# MC_2015.net
KiCad netlist of a schematic drawn in EAGLE
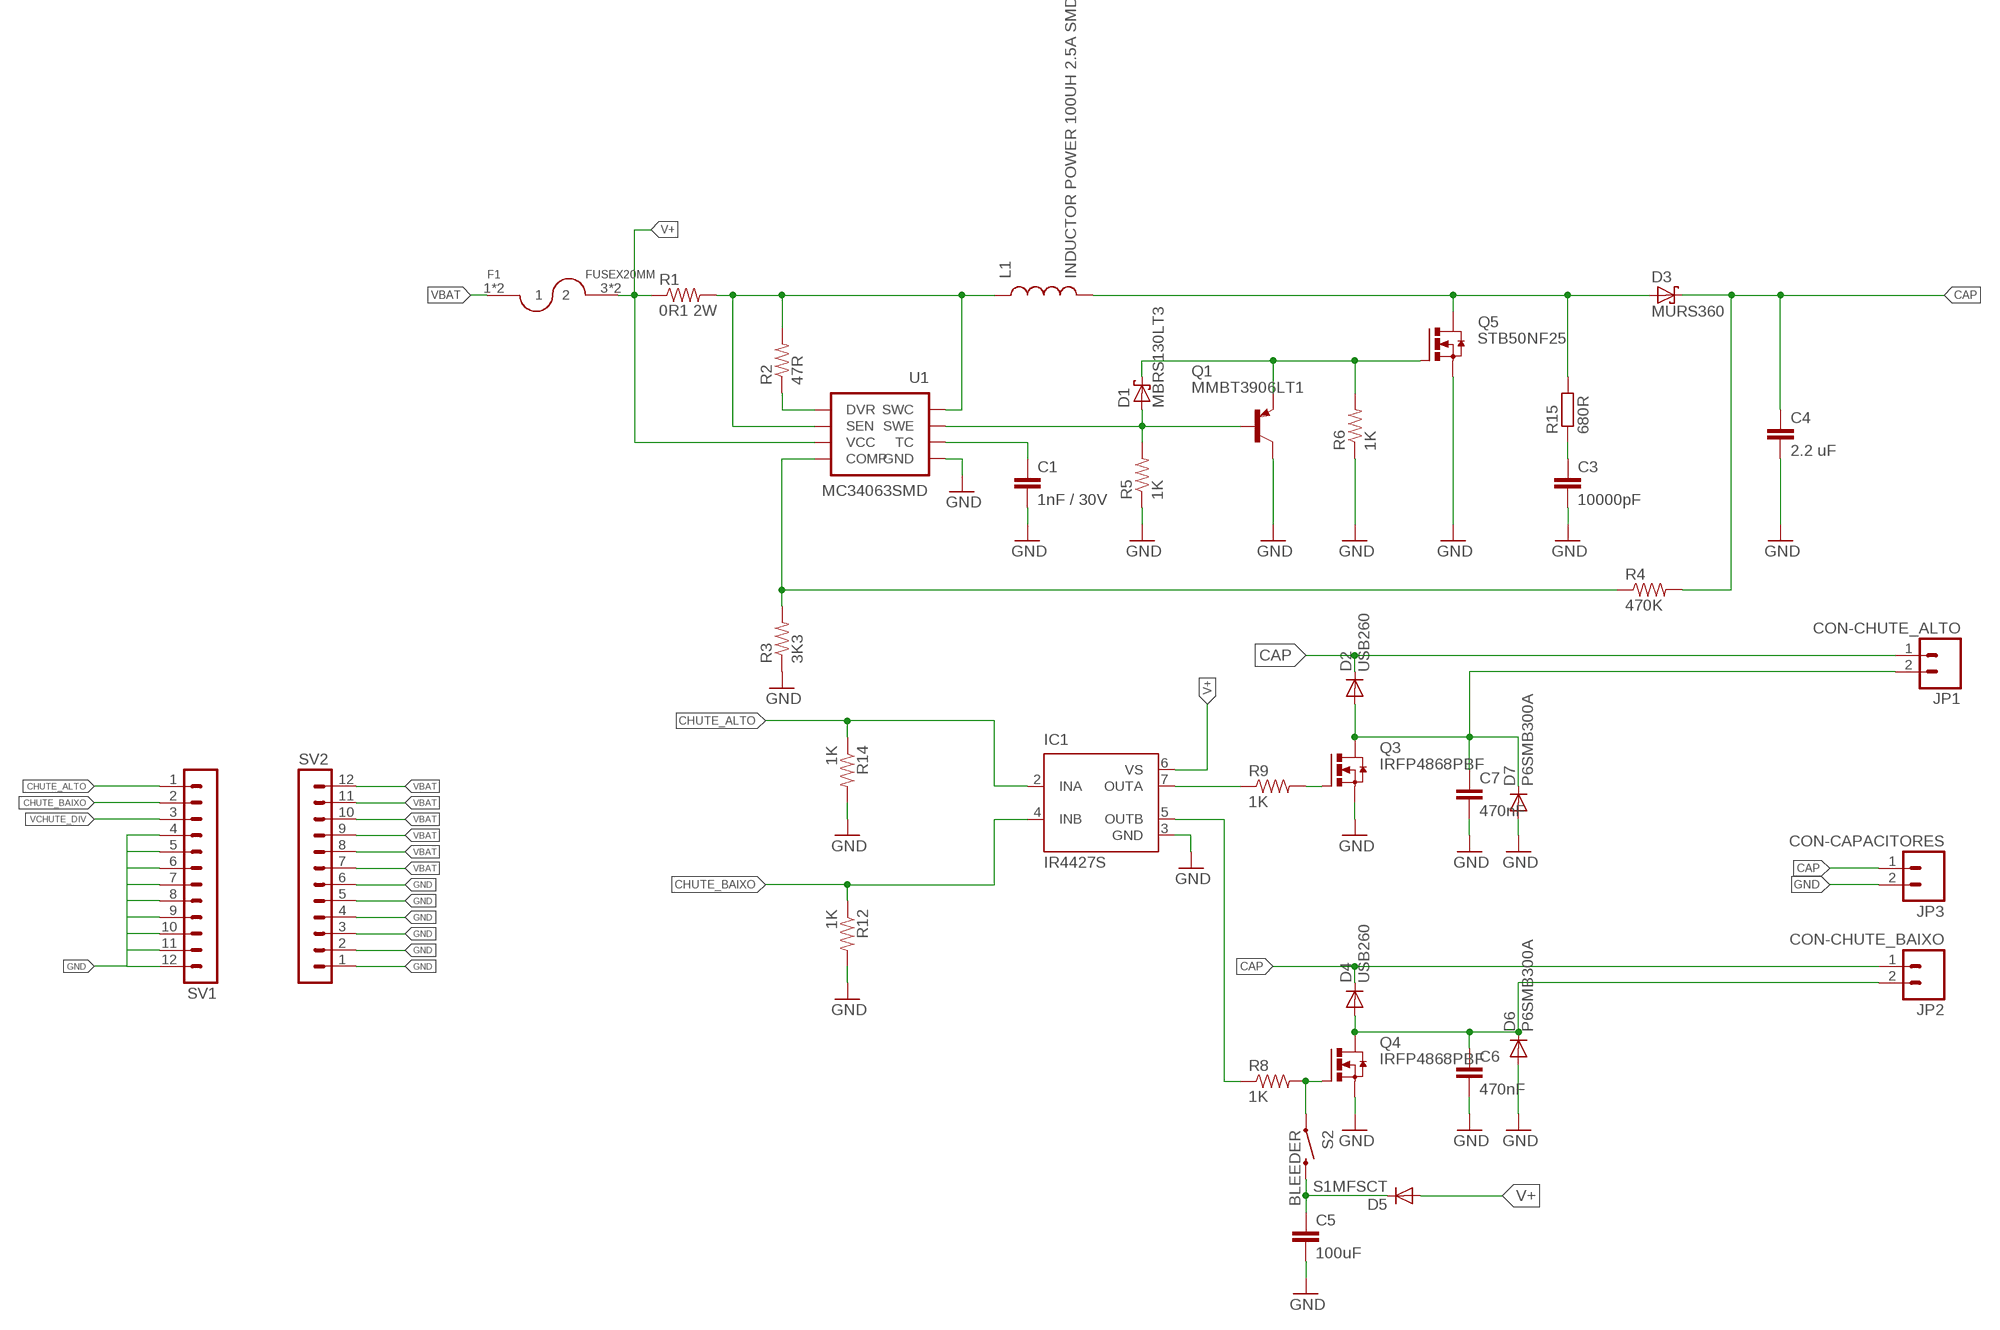
[diagram p0: schematic, sheet 1]

(export (version "E")
  (design (tool "Eeschema 10.0.6"))
  (components
    (comp (ref "C1")
      (value "1nF / 30V")
      (footprint "eagle-import:0805")
      (libsource (lib "eagle-import") (part "CAP0805"))
    )
    (comp (ref "C3")
      (value "10000pF")
      (footprint "eagle-import:1210")
      (libsource (lib "eagle-import") (part "SparkFun-Passives_CAP1210"))
    )
    (comp (ref "C4")
      (value "2.2 uF")
      (footprint "eagle-import:C2220K")
      (libsource (lib "eagle-import") (part "resistor_C-EUC2220K"))
    )
    (comp (ref "C5")
      (value "100uF")
      (footprint "eagle-import:C1210")
      (libsource (lib "eagle-import") (part "resistor_C-EUC1210"))
    )
    (comp (ref "C6")
      (value "470nF")
      (footprint "eagle-import:C1812")
      (libsource (lib "eagle-import") (part "C-EUC1812"))
    )
    (comp (ref "C7")
      (value "470nF")
      (footprint "eagle-import:C1812")
      (libsource (lib "eagle-import") (part "C-EUC1812"))
    )
    (comp (ref "D1")
      (value "MBRS130LT3")
      (footprint "eagle-import:SMB")
      (libsource (lib "eagle-import") (part "MBRS130LT3"))
    )
    (comp (ref "D2")
      (value "USB260")
      (footprint "eagle-import:SMB")
      (libsource (lib "eagle-import") (part "DIODE-SMB"))
    )
    (comp (ref "D3")
      (value "MURS360")
      (footprint "eagle-import:SMC")
      (libsource (lib "eagle-import") (part "SCHOTTKY-DIODESMC"))
    )
    (comp (ref "D4")
      (value "USB260")
      (footprint "eagle-import:SMB")
      (libsource (lib "eagle-import") (part "DIODE-SMB"))
    )
    (comp (ref "D5")
      (value "S1MFSCT")
      (footprint "eagle-import:SMA-DIODE")
      (libsource (lib "eagle-import") (part "DIODESMA"))
    )
    (comp (ref "D6")
      (value "P6SMB300A")
      (footprint "eagle-import:SMB")
      (libsource (lib "eagle-import") (part "DIODE-SMB"))
    )
    (comp (ref "D7")
      (value "P6SMB300A")
      (footprint "eagle-import:SMB")
      (libsource (lib "eagle-import") (part "DIODE-SMB"))
    )
    (comp (ref "F1")
      (value "FUSEX20MM")
      (footprint "eagle-import:FUSE_5MM")
      (libsource (lib "eagle-import") (part "FUSEX20MM"))
    )
    (comp (ref "IC1")
      (value "IR4427S")
      (footprint "eagle-import:SO08")
      (libsource (lib "eagle-import") (part "IR4427S"))
    )
    (comp (ref "JP1")
      (value "CON-CHUTE_ALTO")
      (footprint "eagle-import:SCREWTERMINAL-5MM-2")
      (libsource (lib "eagle-import") (part "M025MM"))
    )
    (comp (ref "JP2")
      (value "CON-CHUTE_BAIXO")
      (footprint "eagle-import:SCREWTERMINAL-5MM-2")
      (libsource (lib "eagle-import") (part "M025MM"))
    )
    (comp (ref "JP3")
      (value "CON-CAPACITORES")
      (footprint "eagle-import:SCREWTERMINAL-5MM-2")
      (libsource (lib "eagle-import") (part "M025MM"))
    )
    (comp (ref "L1")
      (value "INDUCTOR POWER 100UH 2.5A SMD")
      (footprint "eagle-import:CDRH125")
      (libsource (lib "eagle-import") (part "INDUCTORPWR"))
    )
    (comp (ref "Q1")
      (value "MMBT3906LT1")
      (footprint "eagle-import:SOT23-BEC")
      (libsource (lib "eagle-import") (part "MMBT3906SMDLT1"))
    )
    (comp (ref "Q3")
      (value "IRFP4868PBF")
      (footprint "eagle-import:TO247BV")
      (libsource (lib "eagle-import") (part "IRFP240"))
    )
    (comp (ref "Q4")
      (value "IRFP4868PBF")
      (footprint "eagle-import:TO247BV")
      (libsource (lib "eagle-import") (part "IRFP240"))
    )
    (comp (ref "Q5")
      (value "STB50NF25")
      (footprint "eagle-import:D2PACK")
      (libsource (lib "eagle-import") (part "IRF3704S"))
    )
    (comp (ref "R1")
      (value "0R1 2W")
      (footprint "eagle-import:R2512")
      (libsource (lib "eagle-import") (part "RESISTOR2512"))
    )
    (comp (ref "R2")
      (value "47R")
      (footprint "eagle-import:0805")
      (libsource (lib "eagle-import") (part "RESISTOR"))
    )
    (comp (ref "R3")
      (value "3K3")
      (footprint "eagle-import:0805")
      (libsource (lib "eagle-import") (part "RESISTOR"))
    )
    (comp (ref "R4")
      (value "470K")
      (footprint "eagle-import:R2512")
      (libsource (lib "eagle-import") (part "SparkFun-Passives_RESISTOR2512"))
    )
    (comp (ref "R5")
      (value "1K")
      (footprint "eagle-import:0805")
      (libsource (lib "eagle-import") (part "RESISTOR"))
    )
    (comp (ref "R6")
      (value "1K")
      (footprint "eagle-import:0805")
      (libsource (lib "eagle-import") (part "RESISTOR"))
    )
    (comp (ref "R8")
      (value "1K")
      (footprint "eagle-import:0805")
      (libsource (lib "eagle-import") (part "RESISTOR"))
    )
    (comp (ref "R9")
      (value "1K")
      (footprint "eagle-import:0805")
      (libsource (lib "eagle-import") (part "RESISTOR0805-RES"))
    )
    (comp (ref "R12")
      (value "1K")
      (footprint "eagle-import:0805")
      (libsource (lib "eagle-import") (part "RESISTOR"))
    )
    (comp (ref "R14")
      (value "1K")
      (footprint "eagle-import:0805")
      (libsource (lib "eagle-import") (part "RESISTOR"))
    )
    (comp (ref "R15")
      (value "680R")
      (footprint "eagle-import:R1210")
      (libsource (lib "eagle-import") (part "R-EU_R1210"))
    )
    (comp (ref "S2")
      (value "BLEEDER")
      (footprint "eagle-import:TACTILE-PTH")
      (libsource (lib "eagle-import") (part "SWITCH-MOMENTARY-2PTH"))
    )
    (comp (ref "SV1")
      (value "MA12-1")
      (footprint "eagle-import:MA12-1")
      (libsource (lib "eagle-import") (part "MA12-1"))
    )
    (comp (ref "SV2")
      (value "MA12-1")
      (footprint "eagle-import:MA12-1")
      (libsource (lib "eagle-import") (part "MA12-1"))
    )
    (comp (ref "U1")
      (value "MC34063SMD")
      (footprint "eagle-import:SO08")
      (libsource (lib "eagle-import") (part "MC34063SMD"))
    )
  )
  (nets
    (net (code "1") (name "CAP") (class "Default")
      (node (ref "C4") (pin "1") (pinfunction "1_1") (pintype "passive"))
      (node (ref "D2") (pin "C") (pinfunction "C_C") (pintype "passive"))
      (node (ref "D3") (pin "C") (pinfunction "C_C") (pintype "passive"))
      (node (ref "D4") (pin "C") (pinfunction "C_C") (pintype "passive"))
      (node (ref "JP1") (pin "1") (pinfunction "1_1") (pintype "passive"))
      (node (ref "JP2") (pin "1") (pinfunction "1_1") (pintype "passive"))
      (node (ref "JP3") (pin "1") (pinfunction "1_1") (pintype "passive"))
      (node (ref "R4") (pin "2") (pinfunction "2_2") (pintype "passive"))
    )
    (net (code "2") (name "CHUTE_ALTO") (class "Default")
      (node (ref "IC1") (pin "2") (pinfunction "INA_2") (pintype "input"))
      (node (ref "R14") (pin "1") (pinfunction "1_1") (pintype "passive"))
      (node (ref "SV1") (pin "1") (pinfunction "1_1") (pintype "passive"))
    )
    (net (code "3") (name "CHUTE_BAIXO") (class "Default")
      (node (ref "IC1") (pin "4") (pinfunction "INB_4") (pintype "input"))
      (node (ref "R12") (pin "1") (pinfunction "1_1") (pintype "passive"))
      (node (ref "SV1") (pin "2") (pinfunction "2_2") (pintype "passive"))
    )
    (net (code "4") (name "GND") (class "Default")
      (node (ref "C1") (pin "2") (pinfunction "2_2") (pintype "passive"))
      (node (ref "C3") (pin "2") (pinfunction "2_2") (pintype "passive"))
      (node (ref "C4") (pin "2") (pinfunction "2_2") (pintype "passive"))
      (node (ref "C5") (pin "2") (pinfunction "2_2") (pintype "passive"))
      (node (ref "C6") (pin "2") (pinfunction "2_2") (pintype "passive"))
      (node (ref "C7") (pin "2") (pinfunction "2_2") (pintype "passive"))
      (node (ref "D6") (pin "A") (pinfunction "A_A") (pintype "passive"))
      (node (ref "D7") (pin "A") (pinfunction "A_A") (pintype "passive"))
      (node (ref "IC1") (pin "3") (pinfunction "GND_3") (pintype "power_in"))
      (node (ref "JP3") (pin "2") (pinfunction "2_2") (pintype "passive"))
      (node (ref "Q1") (pin "C") (pinfunction "C_C") (pintype "passive"))
      (node (ref "Q3") (pin "S") (pinfunction "S_S") (pintype "passive"))
      (node (ref "Q4") (pin "S") (pinfunction "S_S") (pintype "passive"))
      (node (ref "Q5") (pin "3") (pinfunction "S_3") (pintype "passive"))
      (node (ref "R12") (pin "2") (pinfunction "2_2") (pintype "passive"))
      (node (ref "R14") (pin "2") (pinfunction "2_2") (pintype "passive"))
      (node (ref "R3") (pin "1") (pinfunction "1_1") (pintype "passive"))
      (node (ref "R5") (pin "1") (pinfunction "1_1") (pintype "passive"))
      (node (ref "R6") (pin "1") (pinfunction "1_1") (pintype "passive"))
      (node (ref "SV1") (pin "10") (pinfunction "10_10") (pintype "passive"))
      (node (ref "SV1") (pin "11") (pinfunction "11_11") (pintype "passive"))
      (node (ref "SV1") (pin "12") (pinfunction "12_12") (pintype "passive"))
      (node (ref "SV1") (pin "4") (pinfunction "4_4") (pintype "passive"))
      (node (ref "SV1") (pin "5") (pinfunction "5_5") (pintype "passive"))
      (node (ref "SV1") (pin "6") (pinfunction "6_6") (pintype "passive"))
      (node (ref "SV1") (pin "7") (pinfunction "7_7") (pintype "passive"))
      (node (ref "SV1") (pin "8") (pinfunction "8_8") (pintype "passive"))
      (node (ref "SV1") (pin "9") (pinfunction "9_9") (pintype "passive"))
      (node (ref "SV2") (pin "1") (pinfunction "1_1") (pintype "passive"))
      (node (ref "SV2") (pin "2") (pinfunction "2_2") (pintype "passive"))
      (node (ref "SV2") (pin "3") (pinfunction "3_3") (pintype "passive"))
      (node (ref "SV2") (pin "4") (pinfunction "4_4") (pintype "passive"))
      (node (ref "SV2") (pin "5") (pinfunction "5_5") (pintype "passive"))
      (node (ref "SV2") (pin "6") (pinfunction "6_6") (pintype "passive"))
      (node (ref "U1") (pin "4") (pinfunction "GND_4") (pintype "bidirectional"))
    )
    (net (code "5") (name "Net-(C3-Pad1)") (class "Default")
      (node (ref "C3") (pin "1") (pinfunction "1_1") (pintype "passive"))
      (node (ref "R15") (pin "1") (pinfunction "1_1") (pintype "passive"))
    )
    (net (code "6") (name "Net-(C6-Pad1)") (class "Default")
      (node (ref "C6") (pin "1") (pinfunction "1_1") (pintype "passive"))
      (node (ref "D4") (pin "A") (pinfunction "A_A") (pintype "passive"))
      (node (ref "D6") (pin "C") (pinfunction "C_C") (pintype "passive"))
      (node (ref "JP2") (pin "2") (pinfunction "2_2") (pintype "passive"))
      (node (ref "Q4") (pin "D") (pinfunction "D_D") (pintype "passive"))
    )
    (net (code "7") (name "Net-(C7-Pad1)") (class "Default")
      (node (ref "C7") (pin "1") (pinfunction "1_1") (pintype "passive"))
      (node (ref "D2") (pin "A") (pinfunction "A_A") (pintype "passive"))
      (node (ref "D7") (pin "C") (pinfunction "C_C") (pintype "passive"))
      (node (ref "JP1") (pin "2") (pinfunction "2_2") (pintype "passive"))
      (node (ref "Q3") (pin "D") (pinfunction "D_D") (pintype "passive"))
    )
    (net (code "8") (name "Net-(IC1-OUTA)") (class "Default")
      (node (ref "IC1") (pin "7") (pinfunction "OUTA_7") (pintype "output"))
      (node (ref "R9") (pin "1") (pinfunction "1_1") (pintype "passive"))
    )
    (net (code "9") (name "Net-(IC1-OUTB)") (class "Default")
      (node (ref "IC1") (pin "5") (pinfunction "OUTB_5") (pintype "output"))
      (node (ref "R8") (pin "1") (pinfunction "1_1") (pintype "passive"))
    )
    (net (code "10") (name "Net-(Q3-PadG)") (class "Default")
      (node (ref "Q3") (pin "G") (pinfunction "G_G") (pintype "passive"))
      (node (ref "R9") (pin "2") (pinfunction "2_2") (pintype "passive"))
    )
    (net (code "11") (name "Net-(Q4-PadG)") (class "Default")
      (node (ref "Q4") (pin "G") (pinfunction "G_G") (pintype "passive"))
      (node (ref "R8") (pin "2") (pinfunction "2_2") (pintype "passive"))
      (node (ref "S2") (pin "1") (pinfunction "1_1") (pintype "passive"))
    )
    (net (code "12") (name "Net-(Q5-D)") (class "Default")
      (node (ref "D3") (pin "A") (pinfunction "A_A") (pintype "passive"))
      (node (ref "L1") (pin "2") (pinfunction "2_2") (pintype "passive"))
      (node (ref "Q5") (pin "2") (pinfunction "D_2") (pintype "passive"))
      (node (ref "R15") (pin "2") (pinfunction "2_2") (pintype "passive"))
    )
    (net (code "13") (name "Net-(Q5-G)") (class "Default")
      (node (ref "D1") (pin "C") (pinfunction "C_C") (pintype "passive"))
      (node (ref "Q1") (pin "E") (pinfunction "E_E") (pintype "passive"))
      (node (ref "Q5") (pin "1") (pinfunction "G_1") (pintype "passive"))
      (node (ref "R6") (pin "2") (pinfunction "2_2") (pintype "passive"))
    )
    (net (code "14") (name "Net-(S2-2)") (class "Default")
      (node (ref "C5") (pin "1") (pinfunction "1_1") (pintype "passive"))
      (node (ref "D5") (pin "C") (pinfunction "C_C") (pintype "passive"))
      (node (ref "S2") (pin "3") (pinfunction "2_3") (pintype "passive"))
    )
    (net (code "15") (name "Net-(U1-COMP)") (class "Default")
      (node (ref "R3") (pin "2") (pinfunction "2_2") (pintype "passive"))
      (node (ref "R4") (pin "1") (pinfunction "1_1") (pintype "passive"))
      (node (ref "U1") (pin "5") (pinfunction "COMP_5") (pintype "bidirectional"))
    )
    (net (code "16") (name "Net-(U1-DVR)") (class "Default")
      (node (ref "R2") (pin "1") (pinfunction "1_1") (pintype "passive"))
      (node (ref "U1") (pin "8") (pinfunction "DVR_8") (pintype "bidirectional"))
    )
    (net (code "17") (name "Net-(U1-SEN)") (class "Default")
      (node (ref "L1") (pin "1") (pinfunction "1_1") (pintype "passive"))
      (node (ref "R1") (pin "2") (pinfunction "2_2") (pintype "passive"))
      (node (ref "R2") (pin "2") (pinfunction "2_2") (pintype "passive"))
      (node (ref "U1") (pin "1") (pinfunction "SWC_1") (pintype "bidirectional"))
      (node (ref "U1") (pin "7") (pinfunction "SEN_7") (pintype "bidirectional"))
    )
    (net (code "18") (name "Net-(U1-SWE)") (class "Default")
      (node (ref "D1") (pin "A") (pinfunction "A_A") (pintype "passive"))
      (node (ref "Q1") (pin "B") (pinfunction "B_B") (pintype "passive"))
      (node (ref "R5") (pin "2") (pinfunction "2_2") (pintype "passive"))
      (node (ref "U1") (pin "2") (pinfunction "SWE_2") (pintype "bidirectional"))
    )
    (net (code "19") (name "Net-(U1-TC)") (class "Default")
      (node (ref "C1") (pin "1") (pinfunction "1_1") (pintype "passive"))
      (node (ref "U1") (pin "3") (pinfunction "TC_3") (pintype "bidirectional"))
    )
    (net (code "20") (name "V+") (class "Default")
      (node (ref "D5") (pin "A") (pinfunction "A_A") (pintype "passive"))
      (node (ref "F1") (pin "3") (pinfunction "2_3") (pintype "bidirectional"))
      (node (ref "F1") (pin "4") (pinfunction "2_4") (pintype "bidirectional"))
      (node (ref "IC1") (pin "6") (pinfunction "VS_6") (pintype "power_in"))
      (node (ref "R1") (pin "1") (pinfunction "1_1") (pintype "passive"))
      (node (ref "U1") (pin "6") (pinfunction "VCC_6") (pintype "bidirectional"))
    )
    (net (code "21") (name "VBAT") (class "Default")
      (node (ref "F1") (pin "1") (pinfunction "1_1") (pintype "bidirectional"))
      (node (ref "F1") (pin "2") (pinfunction "1_2") (pintype "bidirectional"))
      (node (ref "SV2") (pin "10") (pinfunction "10_10") (pintype "passive"))
      (node (ref "SV2") (pin "11") (pinfunction "11_11") (pintype "passive"))
      (node (ref "SV2") (pin "12") (pinfunction "12_12") (pintype "passive"))
      (node (ref "SV2") (pin "7") (pinfunction "7_7") (pintype "passive"))
      (node (ref "SV2") (pin "8") (pinfunction "8_8") (pintype "passive"))
      (node (ref "SV2") (pin "9") (pinfunction "9_9") (pintype "passive"))
    )
    (net (code "22") (name "VCHUTE_DIV") (class "Default")
      (node (ref "SV1") (pin "3") (pinfunction "3_3") (pintype "passive"))
    )
  )
)
